# RaspiPower.net
KiCad netlist of a schematic drawn in EAGLE
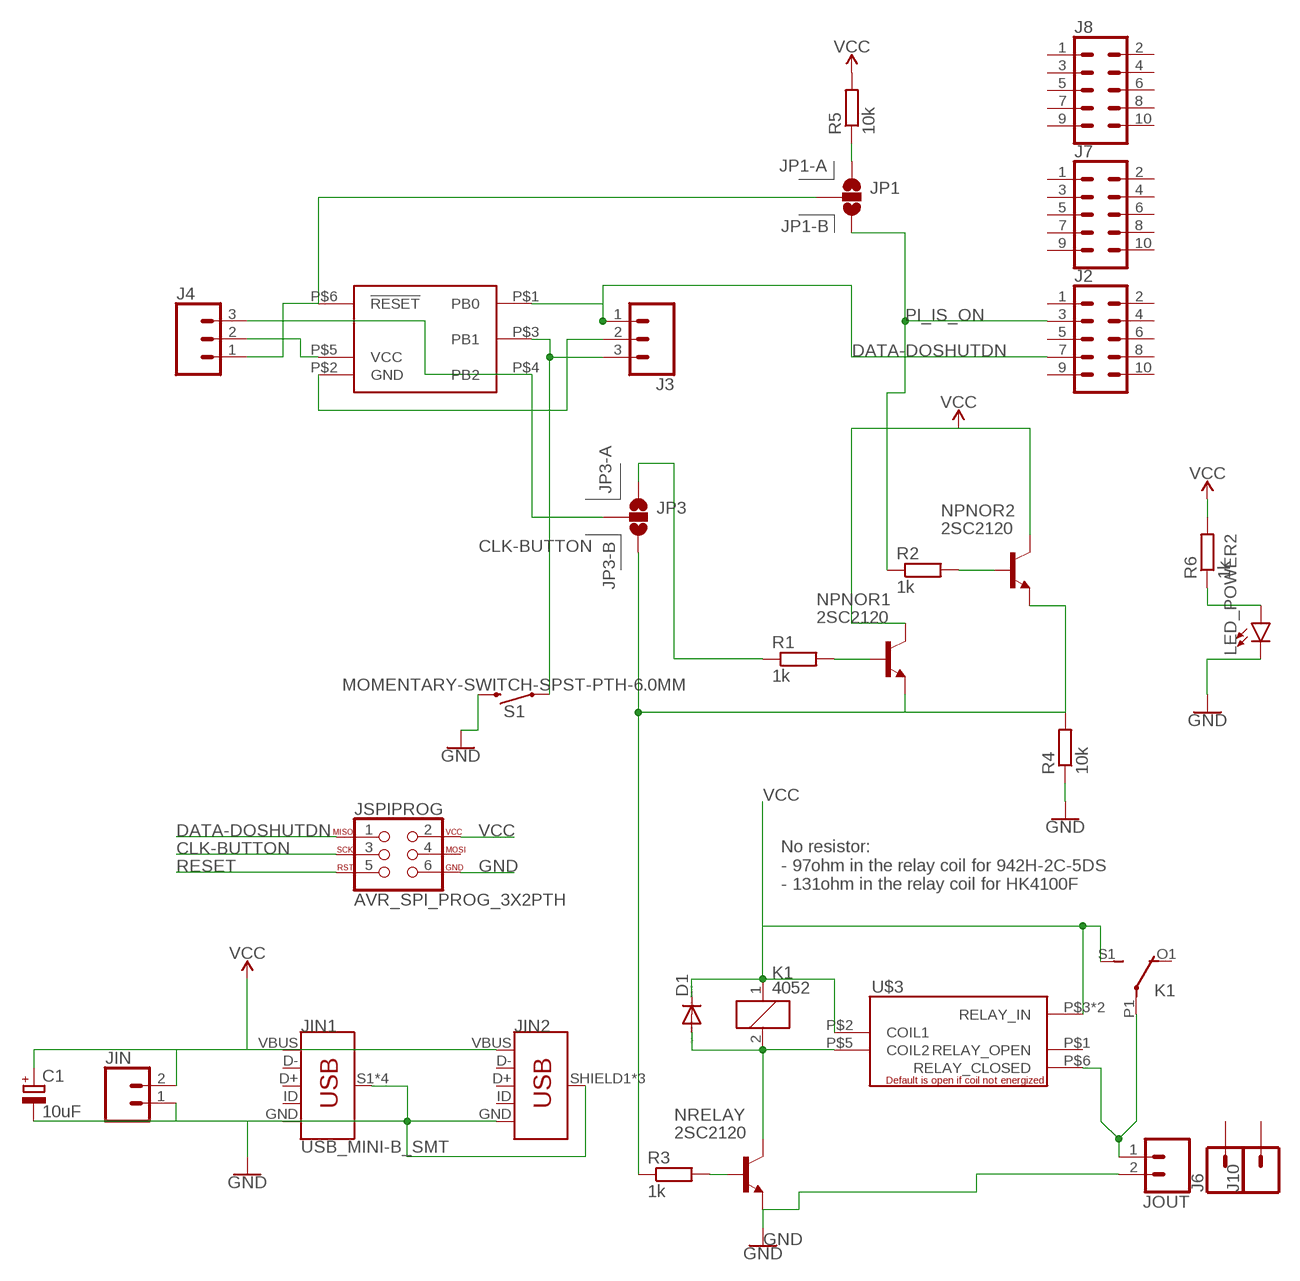
[diagram p0: schematic, sheet 1]

(export (version "E")
  (design (tool "Eeschema 10.0.6"))
  (components
    (comp (ref "C1")
      (value "10uF")
      (footprint "eagle-import:E2,5-5")
      (libsource (lib "eagle-import") (part "CPOL-EUE2.5-5"))
    )
    (comp (ref "D1")
      (value "DIODE-D-5")
      (footprint "eagle-import:D-5")
      (libsource (lib "eagle-import") (part "DIODE-D-5"))
    )
    (comp (ref "J2")
      (value "CONN_05X2PTH")
      (footprint "eagle-import:2X5")
      (libsource (lib "eagle-import") (part "CONN_05X2PTH"))
    )
    (comp (ref "J3")
      (value "CONN_03")
      (footprint "eagle-import:1X03")
      (libsource (lib "eagle-import") (part "CONN_03"))
    )
    (comp (ref "J4")
      (value "CONN_03")
      (footprint "eagle-import:1X03")
      (libsource (lib "eagle-import") (part "CONN_03"))
    )
    (comp (ref "J6")
      (value "CONN_01PTH_NO_SILK_YES_STOP")
      (footprint "eagle-import:1X01_NO_SILK")
      (libsource (lib "eagle-import") (part "CONN_01PTH_NO_SILK_YES_STOP"))
    )
    (comp (ref "J7")
      (value "CONN_05X2PTH")
      (footprint "eagle-import:2X5")
      (libsource (lib "eagle-import") (part "CONN_05X2PTH"))
    )
    (comp (ref "J8")
      (value "CONN_05X2PTH")
      (footprint "eagle-import:2X5")
      (libsource (lib "eagle-import") (part "CONN_05X2PTH"))
    )
    (comp (ref "J10")
      (value "CONN_01PTH_NO_SILK_YES_STOP")
      (footprint "eagle-import:1X01_NO_SILK")
      (libsource (lib "eagle-import") (part "CONN_01PTH_NO_SILK_YES_STOP"))
    )
    (comp (ref "JIN")
      (value "CONN_02LOCK_LONGPADS")
      (footprint "eagle-import:1X02_LOCK_LONGPADS")
      (libsource (lib "eagle-import") (part "CONN_02LOCK_LONGPADS"))
    )
    (comp (ref "JIN1")
      (value "USB_MINI-B_SMT")
      (footprint "eagle-import:USB-MINIB")
      (libsource (lib "eagle-import") (part "USB_MINI-B_SMT"))
    )
    (comp (ref "JIN2")
      (value "USB_MICRO-B_FEMALE-SMT")
      (footprint "eagle-import:USB-B-MICRO-SMD")
      (libsource (lib "eagle-import") (part "USB_MICRO-B_FEMALE-SMT"))
    )
    (comp (ref "JOUT")
      (value "CONN_02LOCK_LONGPADS")
      (footprint "eagle-import:1X02_LOCK_LONGPADS")
      (libsource (lib "eagle-import") (part "CONN_02LOCK_LONGPADS"))
    )
    (comp (ref "JP1")
      (value "JUMPER-SMT_3_NO_SILK")
      (footprint "eagle-import:SMT-JUMPER_3_NO_SILK")
      (libsource (lib "eagle-import") (part "JUMPER-SMT_3_NO_SILK"))
    )
    (comp (ref "JP3")
      (value "JUMPER-SMT_3_NO_SILK")
      (footprint "eagle-import:SMT-JUMPER_3_NO_SILK")
      (libsource (lib "eagle-import") (part "JUMPER-SMT_3_NO_SILK"))
    )
    (comp (ref "JSPIPROG")
      (value "AVR_SPI_PROG_3X2PTH")
      (footprint "eagle-import:2X3")
      (libsource (lib "eagle-import") (part "AVR_SPI_PROG_3X2PTH"))
    )
    (comp (ref "K1")
      (value "4052")
      (footprint "eagle-import:F4052")
      (libsource (lib "eagle-import") (part "4052"))
    )
    (comp (ref "LED_POWER2")
      (value "LED-FKIT-1206")
      (footprint "eagle-import:FKIT-LED-1206")
      (libsource (lib "eagle-import") (part "LED-FKIT-1206"))
    )
    (comp (ref "NPNOR1")
      (value "2SC2120")
      (footprint "eagle-import:TO92-ECB")
      (libsource (lib "eagle-import") (part "-NPN-TO92-ECB"))
    )
    (comp (ref "NPNOR2")
      (value "2SC2120")
      (footprint "eagle-import:TO92-ECB")
      (libsource (lib "eagle-import") (part "-NPN-TO92-ECB"))
    )
    (comp (ref "NRELAY")
      (value "2SC2120")
      (footprint "eagle-import:TO92-ECB")
      (libsource (lib "eagle-import") (part "-NPN-TO92-ECB"))
    )
    (comp (ref "R1")
      (value "1k")
      (footprint "eagle-import:0207_2V")
      (libsource (lib "eagle-import") (part "R-EU_0207/2V"))
    )
    (comp (ref "R2")
      (value "1k")
      (footprint "eagle-import:0207_2V")
      (libsource (lib "eagle-import") (part "R-EU_0207/2V"))
    )
    (comp (ref "R3")
      (value "1k")
      (footprint "eagle-import:0204_7")
      (libsource (lib "eagle-import") (part "R-EU_0204/7"))
    )
    (comp (ref "R4")
      (value "10k")
      (footprint "eagle-import:0207_2V")
      (libsource (lib "eagle-import") (part "R-EU_0207/2V"))
    )
    (comp (ref "R5")
      (value "10k")
      (footprint "eagle-import:0207_2V")
      (libsource (lib "eagle-import") (part "R-EU_0207/2V"))
    )
    (comp (ref "R6")
      (value "1k")
      (footprint "eagle-import:R1206W")
      (libsource (lib "eagle-import") (part "R-EU_R1206W"))
    )
    (comp (ref "S1")
      (value "MOMENTARY-SWITCH-SPST-PTH-6.0MM")
      (footprint "eagle-import:TACTILE_SWITCH_PTH_6.0MM")
      (libsource (lib "eagle-import") (part "MOMENTARY-SWITCH-SPST-PTH-6.0MM"))
    )
    (comp (ref "U$1")
      (value "ATTINY10")
      (footprint "eagle-import:SOT23")
      (libsource (lib "eagle-import") (part "ATTINY10"))
    )
    (comp (ref "U$3")
      (value "HK4100F")
      (footprint "eagle-import:HK4100F")
      (libsource (lib "eagle-import") (part "HK4100F"))
    )
  )
  (nets
    (net (code "1") (name "/CLK-BUTTON") (class "Default")
      (node (ref "J3") (pin "3") (pinfunction "3_3") (pintype "passive"))
      (node (ref "JSPIPROG") (pin "3") (pinfunction "3_3") (pintype "passive"))
      (node (ref "S1") (pin "1") (pinfunction "1_1") (pintype "passive"))
      (node (ref "U$1") (pin "P$3") (pinfunction "PB1_P$3") (pintype "bidirectional"))
    )
    (net (code "2") (name "/DATA-DOSHUTDN") (class "Default")
      (node (ref "J2") (pin "7") (pinfunction "7_7") (pintype "passive"))
      (node (ref "J3") (pin "1") (pinfunction "1_1") (pintype "passive"))
      (node (ref "JSPIPROG") (pin "1") (pinfunction "1_1") (pintype "passive"))
      (node (ref "U$1") (pin "P$1") (pinfunction "PB0_P$1") (pintype "bidirectional"))
    )
    (net (code "3") (name "/PI_IS_ON") (class "Default")
      (node (ref "J2") (pin "3") (pinfunction "3_3") (pintype "passive"))
      (node (ref "JP1") (pin "3") (pinfunction "3_3") (pintype "passive"))
      (node (ref "R2") (pin "1") (pinfunction "1_1") (pintype "passive"))
    )
    (net (code "4") (name "/RESET") (class "Default")
      (node (ref "J4") (pin "1") (pinfunction "1_1") (pintype "passive"))
      (node (ref "JP1") (pin "2") (pinfunction "2_2") (pintype "passive"))
      (node (ref "JSPIPROG") (pin "5") (pinfunction "5_5") (pintype "passive"))
      (node (ref "U$1") (pin "P$6") (pinfunction "~{RESET}_P$6") (pintype "bidirectional"))
    )
    (net (code "5") (name "GND") (class "Default")
      (node (ref "C1") (pin "-") (pinfunction "-_-") (pintype "passive"))
      (node (ref "J3") (pin "2") (pinfunction "2_2") (pintype "passive"))
      (node (ref "JIN") (pin "1") (pinfunction "1_1") (pintype "passive"))
      (node (ref "JIN1") (pin "GND") (pinfunction "GND_GND") (pintype "power_in"))
      (node (ref "JIN1") (pin "S1") (pinfunction "SHIELD_S1") (pintype "bidirectional"))
      (node (ref "JIN1") (pin "S2") (pinfunction "SHIELD_S2") (pintype "bidirectional"))
      (node (ref "JIN1") (pin "S3") (pinfunction "SHIELD_S3") (pintype "bidirectional"))
      (node (ref "JIN1") (pin "S4") (pinfunction "SHIELD_S4") (pintype "bidirectional"))
      (node (ref "JIN2") (pin "GND") (pinfunction "GND_GND") (pintype "power_in"))
      (node (ref "JIN2") (pin "SHIELD1") (pinfunction "SHIELD_SHIELD1") (pintype "bidirectional"))
      (node (ref "JIN2") (pin "SHIELD2") (pinfunction "SHIELD_SHIELD2") (pintype "bidirectional"))
      (node (ref "JIN2") (pin "SHIELD3") (pinfunction "SHIELD_SHIELD3") (pintype "bidirectional"))
      (node (ref "JOUT") (pin "2") (pinfunction "2_2") (pintype "passive"))
      (node (ref "JSPIPROG") (pin "6") (pinfunction "6_6") (pintype "passive"))
      (node (ref "LED_POWER2") (pin "C") (pinfunction "C_C") (pintype "passive"))
      (node (ref "NRELAY") (pin "E") (pinfunction "E_E") (pintype "passive"))
      (node (ref "R4") (pin "1") (pinfunction "1_1") (pintype "passive"))
      (node (ref "S1") (pin "3") (pinfunction "2_3") (pintype "passive"))
      (node (ref "U$1") (pin "P$2") (pinfunction "GND_P$2") (pintype "bidirectional"))
    )
    (net (code "6") (name "Net-(JP1-Pad1)") (class "Default")
      (node (ref "JP1") (pin "1") (pinfunction "1_1") (pintype "passive"))
      (node (ref "R5") (pin "1") (pinfunction "1_1") (pintype "passive"))
    )
    (net (code "7") (name "Net-(JP3-Pad1)") (class "Default")
      (node (ref "JP3") (pin "1") (pinfunction "1_1") (pintype "passive"))
      (node (ref "R1") (pin "1") (pinfunction "1_1") (pintype "passive"))
    )
    (net (code "8") (name "Net-(JP3-Pad3)") (class "Default")
      (node (ref "JP3") (pin "3") (pinfunction "3_3") (pintype "passive"))
      (node (ref "NPNOR1") (pin "E") (pinfunction "E_E") (pintype "passive"))
      (node (ref "NPNOR2") (pin "E") (pinfunction "E_E") (pintype "passive"))
      (node (ref "R3") (pin "1") (pinfunction "1_1") (pintype "passive"))
      (node (ref "R4") (pin "2") (pinfunction "2_2") (pintype "passive"))
    )
    (net (code "9") (name "Net-(K1B-P)") (class "Default")
      (node (ref "JOUT") (pin "1") (pinfunction "1_1") (pintype "passive"))
      (node (ref "K1") (pin "P1") (pinfunction "P_P1") (pintype "passive"))
      (node (ref "U$3") (pin "P$6") (pinfunction "RELAY_CLOSED_P$6") (pintype "bidirectional"))
    )
    (net (code "10") (name "Net-(LED_POWER2-PadA)") (class "Default")
      (node (ref "LED_POWER2") (pin "A") (pinfunction "A_A") (pintype "passive"))
      (node (ref "R6") (pin "1") (pinfunction "1_1") (pintype "passive"))
    )
    (net (code "11") (name "Net-(NPNOR1-PadB)") (class "Default")
      (node (ref "NPNOR1") (pin "B") (pinfunction "B_B") (pintype "passive"))
      (node (ref "R1") (pin "2") (pinfunction "2_2") (pintype "passive"))
    )
    (net (code "12") (name "Net-(NPNOR2-PadB)") (class "Default")
      (node (ref "NPNOR2") (pin "B") (pinfunction "B_B") (pintype "passive"))
      (node (ref "R2") (pin "2") (pinfunction "2_2") (pintype "passive"))
    )
    (net (code "13") (name "Net-(NRELAY-PadB)") (class "Default")
      (node (ref "NRELAY") (pin "B") (pinfunction "B_B") (pintype "passive"))
      (node (ref "R3") (pin "2") (pinfunction "2_2") (pintype "passive"))
    )
    (net (code "14") (name "Net-(U$1-PB2)") (class "Default")
      (node (ref "J4") (pin "3") (pinfunction "3_3") (pintype "passive"))
      (node (ref "JP3") (pin "2") (pinfunction "2_2") (pintype "passive"))
      (node (ref "U$1") (pin "P$4") (pinfunction "PB2_P$4") (pintype "bidirectional"))
    )
    (net (code "15") (name "Net-(U$3-COIL2)") (class "Default")
      (node (ref "D1") (pin "A") (pinfunction "A_A") (pintype "passive"))
      (node (ref "K1") (pin "2") (pinfunction "2_2") (pintype "passive"))
      (node (ref "NRELAY") (pin "C") (pinfunction "C_C") (pintype "passive"))
      (node (ref "U$3") (pin "P$5") (pinfunction "COIL2_P$5") (pintype "bidirectional"))
    )
    (net (code "16") (name "VCC") (class "Default")
      (node (ref "C1") (pin "+") (pinfunction "+_+") (pintype "passive"))
      (node (ref "D1") (pin "C") (pinfunction "C_C") (pintype "passive"))
      (node (ref "J4") (pin "2") (pinfunction "2_2") (pintype "passive"))
      (node (ref "JIN") (pin "2") (pinfunction "2_2") (pintype "passive"))
      (node (ref "JIN1") (pin "VBUS") (pinfunction "VBUS_VBUS") (pintype "power_in"))
      (node (ref "JIN2") (pin "VBUS") (pinfunction "VBUS_VBUS") (pintype "power_in"))
      (node (ref "JSPIPROG") (pin "2") (pinfunction "2_2") (pintype "passive"))
      (node (ref "K1") (pin "1") (pinfunction "1_1") (pintype "passive"))
      (node (ref "K1") (pin "S1") (pinfunction "S_S1") (pintype "passive"))
      (node (ref "NPNOR1") (pin "C") (pinfunction "C_C") (pintype "passive"))
      (node (ref "NPNOR2") (pin "C") (pinfunction "C_C") (pintype "passive"))
      (node (ref "R5") (pin "2") (pinfunction "2_2") (pintype "passive"))
      (node (ref "R6") (pin "2") (pinfunction "2_2") (pintype "passive"))
      (node (ref "U$1") (pin "P$5") (pinfunction "VCC_P$5") (pintype "bidirectional"))
      (node (ref "U$3") (pin "P$2") (pinfunction "COIL1_P$2") (pintype "bidirectional"))
      (node (ref "U$3") (pin "P$3") (pinfunction "RELAY_IN_P$3") (pintype "bidirectional"))
      (node (ref "U$3") (pin "P$4") (pinfunction "RELAY_IN_P$4") (pintype "bidirectional"))
    )
    (net (code "17") (name "unconnected-(J2-Pad1)") (class "Default")
      (node (ref "J2") (pin "1") (pinfunction "1_1") (pintype "passive"))
    )
    (net (code "18") (name "unconnected-(J2-Pad2)") (class "Default")
      (node (ref "J2") (pin "2") (pinfunction "2_2") (pintype "passive"))
    )
    (net (code "19") (name "unconnected-(J2-Pad4)") (class "Default")
      (node (ref "J2") (pin "4") (pinfunction "4_4") (pintype "passive"))
    )
    (net (code "20") (name "unconnected-(J2-Pad5)") (class "Default")
      (node (ref "J2") (pin "5") (pinfunction "5_5") (pintype "passive"))
    )
    (net (code "21") (name "unconnected-(J2-Pad6)") (class "Default")
      (node (ref "J2") (pin "6") (pinfunction "6_6") (pintype "passive"))
    )
    (net (code "22") (name "unconnected-(J2-Pad8)") (class "Default")
      (node (ref "J2") (pin "8") (pinfunction "8_8") (pintype "passive"))
    )
    (net (code "23") (name "unconnected-(J2-Pad9)") (class "Default")
      (node (ref "J2") (pin "9") (pinfunction "9_9") (pintype "passive"))
    )
    (net (code "24") (name "unconnected-(J2-Pad10)") (class "Default")
      (node (ref "J2") (pin "10") (pinfunction "10_10") (pintype "passive"))
    )
    (net (code "25") (name "unconnected-(J6-Pad1)") (class "Default")
      (node (ref "J6") (pin "1") (pinfunction "1_1") (pintype "passive"))
    )
    (net (code "26") (name "unconnected-(J7-Pad1)") (class "Default")
      (node (ref "J7") (pin "1") (pinfunction "1_1") (pintype "passive"))
    )
    (net (code "27") (name "unconnected-(J7-Pad2)") (class "Default")
      (node (ref "J7") (pin "2") (pinfunction "2_2") (pintype "passive"))
    )
    (net (code "28") (name "unconnected-(J7-Pad3)") (class "Default")
      (node (ref "J7") (pin "3") (pinfunction "3_3") (pintype "passive"))
    )
    (net (code "29") (name "unconnected-(J7-Pad4)") (class "Default")
      (node (ref "J7") (pin "4") (pinfunction "4_4") (pintype "passive"))
    )
    (net (code "30") (name "unconnected-(J7-Pad5)") (class "Default")
      (node (ref "J7") (pin "5") (pinfunction "5_5") (pintype "passive"))
    )
    (net (code "31") (name "unconnected-(J7-Pad6)") (class "Default")
      (node (ref "J7") (pin "6") (pinfunction "6_6") (pintype "passive"))
    )
    (net (code "32") (name "unconnected-(J7-Pad7)") (class "Default")
      (node (ref "J7") (pin "7") (pinfunction "7_7") (pintype "passive"))
    )
    (net (code "33") (name "unconnected-(J7-Pad8)") (class "Default")
      (node (ref "J7") (pin "8") (pinfunction "8_8") (pintype "passive"))
    )
    (net (code "34") (name "unconnected-(J7-Pad9)") (class "Default")
      (node (ref "J7") (pin "9") (pinfunction "9_9") (pintype "passive"))
    )
    (net (code "35") (name "unconnected-(J7-Pad10)") (class "Default")
      (node (ref "J7") (pin "10") (pinfunction "10_10") (pintype "passive"))
    )
    (net (code "36") (name "unconnected-(J8-Pad1)") (class "Default")
      (node (ref "J8") (pin "1") (pinfunction "1_1") (pintype "passive"))
    )
    (net (code "37") (name "unconnected-(J8-Pad2)") (class "Default")
      (node (ref "J8") (pin "2") (pinfunction "2_2") (pintype "passive"))
    )
    (net (code "38") (name "unconnected-(J8-Pad3)") (class "Default")
      (node (ref "J8") (pin "3") (pinfunction "3_3") (pintype "passive"))
    )
    (net (code "39") (name "unconnected-(J8-Pad4)") (class "Default")
      (node (ref "J8") (pin "4") (pinfunction "4_4") (pintype "passive"))
    )
    (net (code "40") (name "unconnected-(J8-Pad5)") (class "Default")
      (node (ref "J8") (pin "5") (pinfunction "5_5") (pintype "passive"))
    )
    (net (code "41") (name "unconnected-(J8-Pad6)") (class "Default")
      (node (ref "J8") (pin "6") (pinfunction "6_6") (pintype "passive"))
    )
    (net (code "42") (name "unconnected-(J8-Pad7)") (class "Default")
      (node (ref "J8") (pin "7") (pinfunction "7_7") (pintype "passive"))
    )
    (net (code "43") (name "unconnected-(J8-Pad8)") (class "Default")
      (node (ref "J8") (pin "8") (pinfunction "8_8") (pintype "passive"))
    )
    (net (code "44") (name "unconnected-(J8-Pad9)") (class "Default")
      (node (ref "J8") (pin "9") (pinfunction "9_9") (pintype "passive"))
    )
    (net (code "45") (name "unconnected-(J8-Pad10)") (class "Default")
      (node (ref "J8") (pin "10") (pinfunction "10_10") (pintype "passive"))
    )
    (net (code "46") (name "unconnected-(J10-Pad1)") (class "Default")
      (node (ref "J10") (pin "1") (pinfunction "1_1") (pintype "passive"))
    )
    (net (code "47") (name "unconnected-(JIN1-PadD+)") (class "Default")
      (node (ref "JIN1") (pin "D+") (pinfunction "D+_D+") (pintype "bidirectional"))
    )
    (net (code "48") (name "unconnected-(JIN1-PadD-)") (class "Default")
      (node (ref "JIN1") (pin "D-") (pinfunction "D-_D-") (pintype "bidirectional"))
    )
    (net (code "49") (name "unconnected-(JIN1-PadID)") (class "Default")
      (node (ref "JIN1") (pin "ID") (pinfunction "ID_ID") (pintype "bidirectional"))
    )
    (net (code "50") (name "unconnected-(JIN2-PadD+)") (class "Default")
      (node (ref "JIN2") (pin "D+") (pinfunction "D+_D+") (pintype "bidirectional"))
    )
    (net (code "51") (name "unconnected-(JIN2-PadD-)") (class "Default")
      (node (ref "JIN2") (pin "D-") (pinfunction "D-_D-") (pintype "bidirectional"))
    )
    (net (code "52") (name "unconnected-(JIN2-PadID)") (class "Default")
      (node (ref "JIN2") (pin "ID") (pinfunction "ID_ID") (pintype "bidirectional"))
    )
    (net (code "53") (name "unconnected-(JSPIPROG-Pad4)") (class "Default")
      (node (ref "JSPIPROG") (pin "4") (pinfunction "4_4") (pintype "passive"))
    )
    (net (code "54") (name "unconnected-(K1B-O-PadO1)") (class "Default")
      (node (ref "K1") (pin "O1") (pinfunction "O_O1") (pintype "passive"))
    )
    (net (code "55") (name "unconnected-(U$3-RELAY_OPEN-PadP$1)") (class "Default")
      (node (ref "U$3") (pin "P$1") (pinfunction "RELAY_OPEN_P$1") (pintype "bidirectional"))
    )
  )
)
